# Communications_Chip.net
KiCad netlist of a schematic drawn in Altium Designer
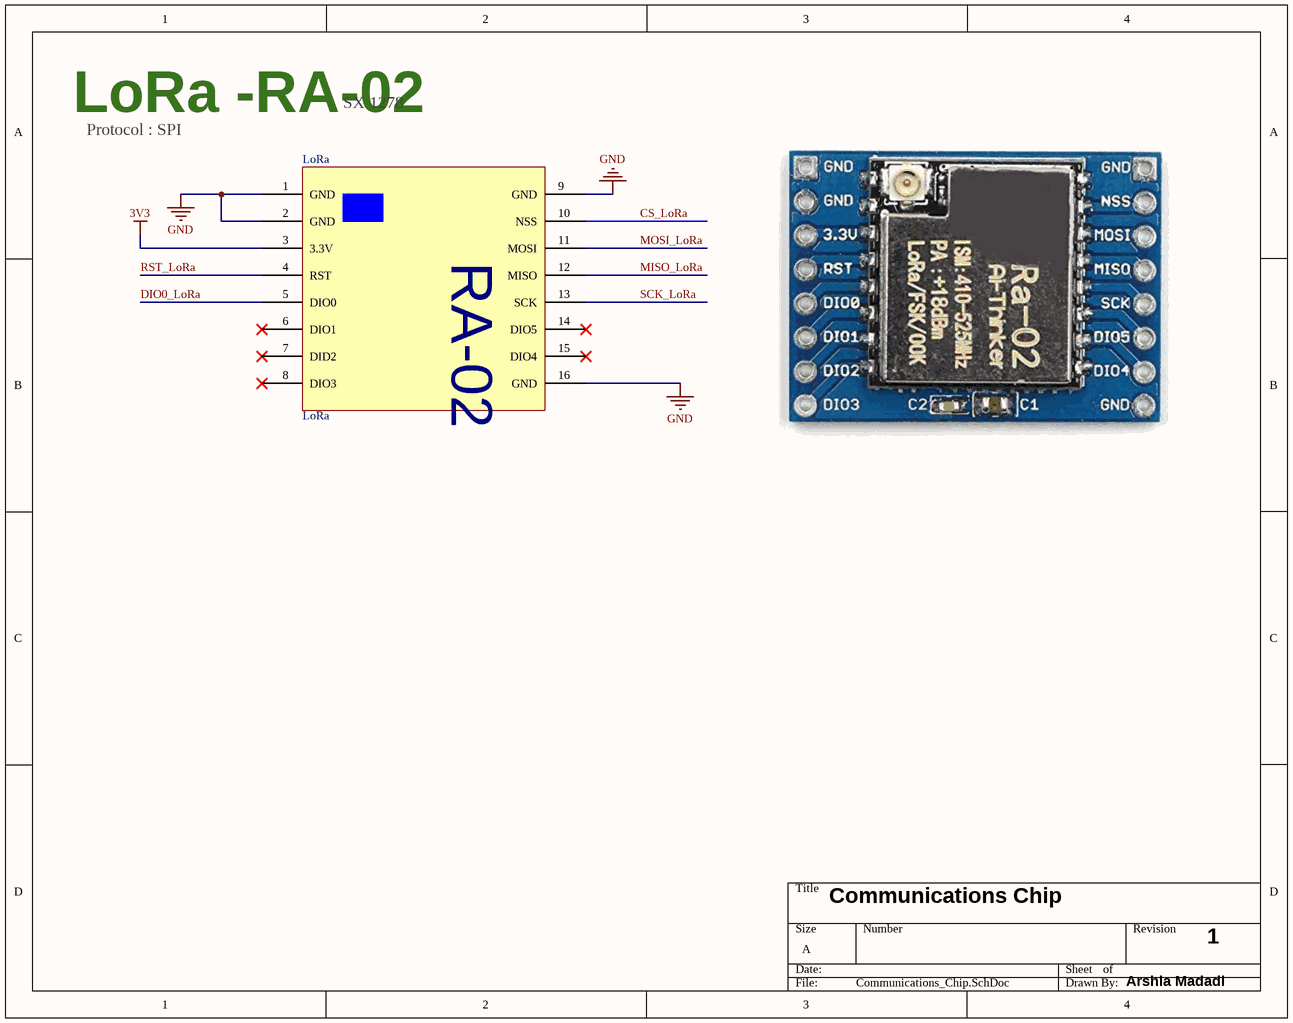
[diagram p0: Communications_Chip.SchDoc]

(export (version "E")
  (design (tool "Eeschema 10.0.6"))
  (components
    (comp (ref "LoRa") (value "LoRa") (footprint "PCBComponent_1") (libsource (lib "LoRa") (part "LoRa")))
  )
  (nets
    (net (code "1") (name "/CS_LoRa") (class "Default")
      (node (ref "LoRa") (pin "10") (pinfunction "NSS_10") (pintype "passive"))
    )
    (net (code "2") (name "/DIO0_LoRa") (class "Default")
      (node (ref "LoRa") (pin "5") (pinfunction "DIO0_5") (pintype "passive"))
    )
    (net (code "3") (name "/MISO_LoRa") (class "Default")
      (node (ref "LoRa") (pin "12") (pinfunction "MISO_12") (pintype "passive"))
    )
    (net (code "4") (name "/MOSI_LoRa") (class "Default")
      (node (ref "LoRa") (pin "11") (pinfunction "MOSI_11") (pintype "passive"))
    )
    (net (code "5") (name "/RST_LoRa") (class "Default")
      (node (ref "LoRa") (pin "4") (pinfunction "RST_4") (pintype "passive"))
    )
    (net (code "6") (name "/SCK_LoRa") (class "Default")
      (node (ref "LoRa") (pin "13") (pinfunction "SCK_13") (pintype "passive"))
    )
    (net (code "7") (name "3V3") (class "Default")
      (node (ref "LoRa") (pin "3") (pinfunction "3.3V_3") (pintype "passive"))
    )
    (net (code "8") (name "GND") (class "Default")
      (node (ref "LoRa") (pin "1") (pinfunction "GND_1") (pintype "passive"))
      (node (ref "LoRa") (pin "16") (pinfunction "GND_16") (pintype "passive"))
      (node (ref "LoRa") (pin "2") (pinfunction "GND_2") (pintype "passive"))
      (node (ref "LoRa") (pin "9") (pinfunction "GND_9") (pintype "passive"))
    )
    (net (code "9") (name "unconnected-(LoRa-DID2-Pad7)") (class "Default")
      (node (ref "LoRa") (pin "7") (pinfunction "DID2_7") (pintype "passive+no_connect"))
    )
    (net (code "10") (name "unconnected-(LoRa-DIO1-Pad6)") (class "Default")
      (node (ref "LoRa") (pin "6") (pinfunction "DIO1_6") (pintype "passive+no_connect"))
    )
    (net (code "11") (name "unconnected-(LoRa-DIO3-Pad8)") (class "Default")
      (node (ref "LoRa") (pin "8") (pinfunction "DIO3_8") (pintype "passive+no_connect"))
    )
    (net (code "12") (name "unconnected-(LoRa-DIO4-Pad15)") (class "Default")
      (node (ref "LoRa") (pin "15") (pinfunction "DIO4_15") (pintype "passive+no_connect"))
    )
    (net (code "13") (name "unconnected-(LoRa-DIO5-Pad14)") (class "Default")
      (node (ref "LoRa") (pin "14") (pinfunction "DIO5_14") (pintype "passive+no_connect"))
    )
  )
)
